# lyte-byte-pcb.net
KiCad netlist of a schematic drawn in EAGLE
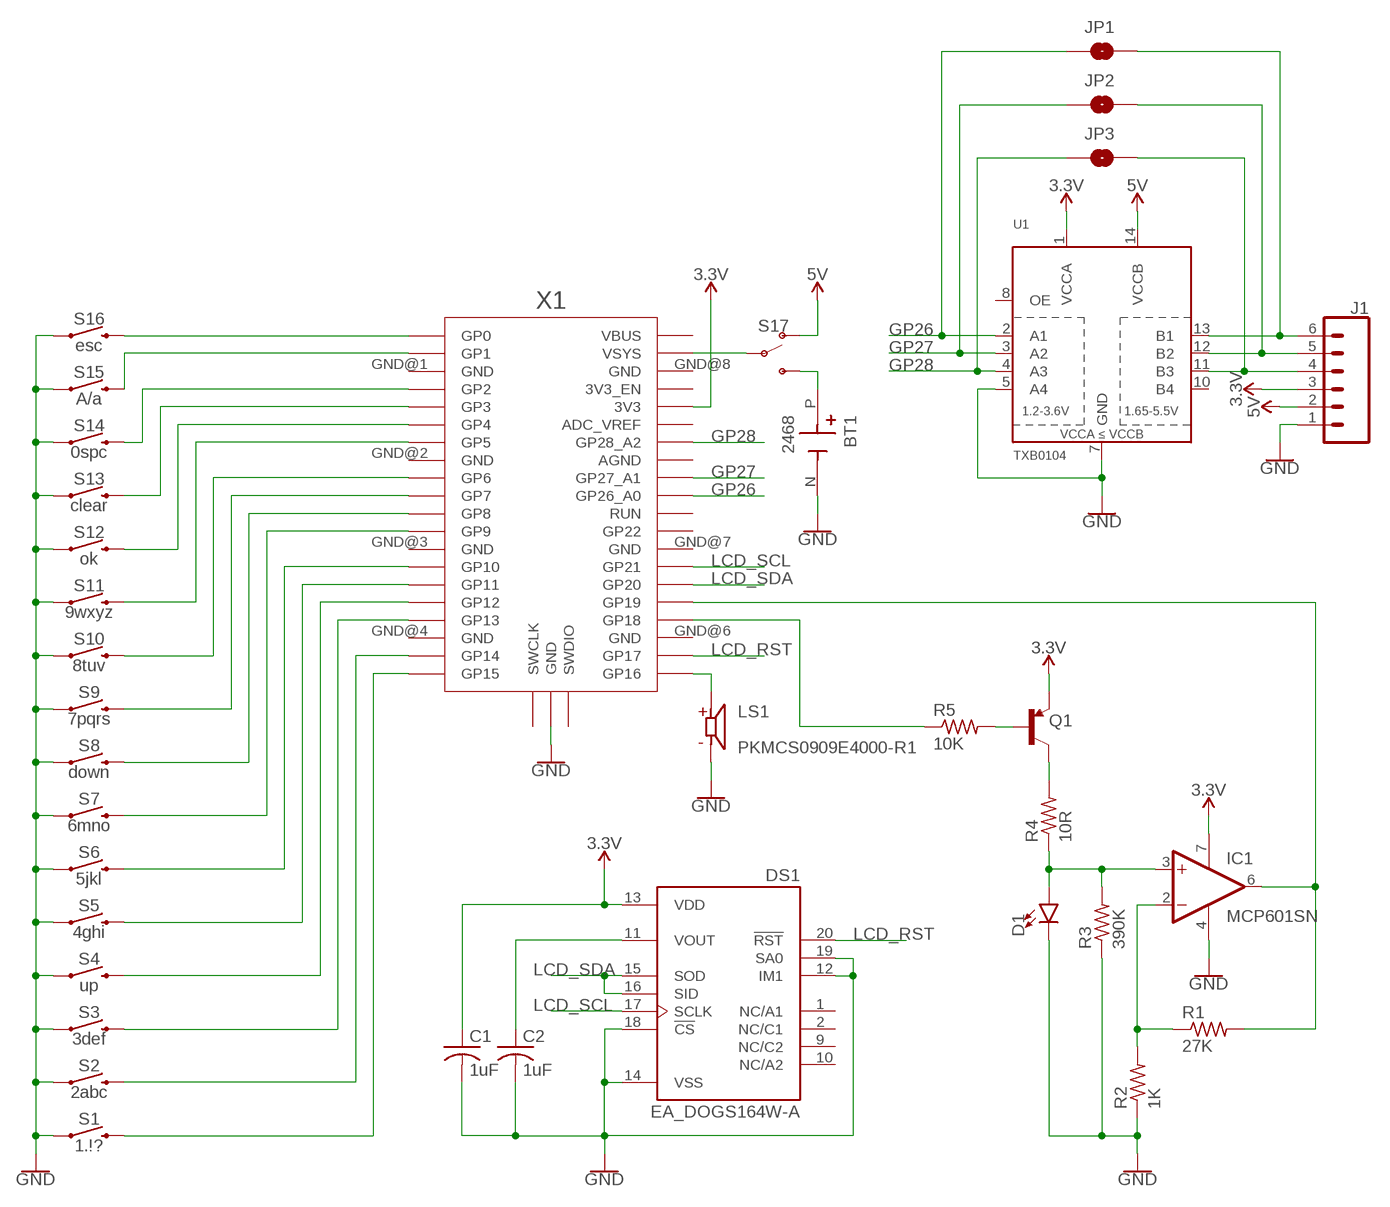
[diagram p0: schematic, sheet 1]

(export (version "E")
  (design (tool "Eeschema 10.0.6"))
  (components
    (comp (ref "BT1")
      (value "2468")
      (footprint "eagle-import:BAT_2468")
      (fields (field (name "MANUFACTURER") "Keystone"))
      (libsource (lib "eagle-import") (part "2468"))
    )
    (comp (ref "C1")
      (value "1uF")
      (footprint "eagle-import:C1206")
      (libsource (lib "eagle-import") (part "C-USC1206"))
    )
    (comp (ref "C2")
      (value "1uF")
      (footprint "eagle-import:C1206")
      (libsource (lib "eagle-import") (part "C-USC1206"))
    )
    (comp (ref "D1")
      (value "LED5MM")
      (footprint "eagle-import:LED_5MM")
      (libsource (lib "eagle-import") (part "LED5MM"))
    )
    (comp (ref "DS1")
      (value "EA_DOGS164W-A")
      (footprint "eagle-import:LCD_EA_DOGS164W-A")
      (fields (field (name "MANUFACTURER") "Display Visions"))
      (libsource (lib "eagle-import") (part "EA_DOGS164W-A"))
    )
    (comp (ref "IC1")
      (value "MCP601SN")
      (footprint "eagle-import:SO08")
      (libsource (lib "eagle-import") (part "MCP601SN"))
    )
    (comp (ref "J1")
      (value "CONN_06SILK_FEMALE_PTH")
      (footprint "eagle-import:1X06")
      (libsource (lib "eagle-import") (part "CONN_06SILK_FEMALE_PTH"))
    )
    (comp (ref "JP1")
      (value "JUMPER-SMT_2_NO_NO-SILK")
      (footprint "eagle-import:SMT-JUMPER_2_NO_NO-SILK")
      (libsource (lib "eagle-import") (part "JUMPER-SMT_2_NO_NO-SILK"))
    )
    (comp (ref "JP2")
      (value "JUMPER-SMT_2_NO_NO-SILK")
      (footprint "eagle-import:SMT-JUMPER_2_NO_NO-SILK")
      (libsource (lib "eagle-import") (part "JUMPER-SMT_2_NO_NO-SILK"))
    )
    (comp (ref "JP3")
      (value "JUMPER-SMT_2_NO_NO-SILK")
      (footprint "eagle-import:SMT-JUMPER_2_NO_NO-SILK")
      (libsource (lib "eagle-import") (part "JUMPER-SMT_2_NO_NO-SILK"))
    )
    (comp (ref "LS1")
      (value "PKMCS0909E4000-R1")
      (footprint "eagle-import:SPKR_PKMCS0909E4000-R1")
      (fields (field (name "MANUFACTURER") "Murata Electronics"))
      (libsource (lib "eagle-import") (part "PKMCS0909E4000-R1"))
    )
    (comp (ref "Q1")
      (value "TRANS_PNP-PMBT3906|MMBT3906L")
      (footprint "eagle-import:SOT23-3")
      (libsource (lib "eagle-import") (part "TRANS_PNP-PMBT3906|MMBT3906L"))
    )
    (comp (ref "R1")
      (value "27K")
      (footprint "eagle-import:R1206")
      (libsource (lib "eagle-import") (part "R-US_R1206"))
    )
    (comp (ref "R2")
      (value "1K")
      (footprint "eagle-import:R1206")
      (libsource (lib "eagle-import") (part "R-US_R1206"))
    )
    (comp (ref "R3")
      (value "390K")
      (footprint "eagle-import:R1206")
      (libsource (lib "eagle-import") (part "R-US_R1206"))
    )
    (comp (ref "R4")
      (value "10R")
      (footprint "eagle-import:R1206")
      (libsource (lib "eagle-import") (part "R-US_R1206"))
    )
    (comp (ref "R5")
      (value "10K")
      (footprint "eagle-import:R1206")
      (libsource (lib "eagle-import") (part "R-US_R1206"))
    )
    (comp (ref "S1")
      (value "1.\\!?")
      (footprint "eagle-import:TACTILE_SWITCH_SMD_5.2MM")
      (libsource (lib "eagle-import") (part "MOMENTARY-SWITCH-SPST-SMD-5.2MM"))
    )
    (comp (ref "S2")
      (value "2abc")
      (footprint "eagle-import:TACTILE_SWITCH_SMD_5.2MM")
      (libsource (lib "eagle-import") (part "MOMENTARY-SWITCH-SPST-SMD-5.2MM"))
    )
    (comp (ref "S3")
      (value "3def")
      (footprint "eagle-import:TACTILE_SWITCH_SMD_5.2MM")
      (libsource (lib "eagle-import") (part "MOMENTARY-SWITCH-SPST-SMD-5.2MM"))
    )
    (comp (ref "S4")
      (value "up")
      (footprint "eagle-import:TACTILE_SWITCH_SMD_5.2MM")
      (libsource (lib "eagle-import") (part "MOMENTARY-SWITCH-SPST-SMD-5.2MM"))
    )
    (comp (ref "S5")
      (value "4ghi")
      (footprint "eagle-import:TACTILE_SWITCH_SMD_5.2MM")
      (libsource (lib "eagle-import") (part "MOMENTARY-SWITCH-SPST-SMD-5.2MM"))
    )
    (comp (ref "S6")
      (value "5jkl")
      (footprint "eagle-import:TACTILE_SWITCH_SMD_5.2MM")
      (libsource (lib "eagle-import") (part "MOMENTARY-SWITCH-SPST-SMD-5.2MM"))
    )
    (comp (ref "S7")
      (value "6mno")
      (footprint "eagle-import:TACTILE_SWITCH_SMD_5.2MM")
      (libsource (lib "eagle-import") (part "MOMENTARY-SWITCH-SPST-SMD-5.2MM"))
    )
    (comp (ref "S8")
      (value "down")
      (footprint "eagle-import:TACTILE_SWITCH_SMD_5.2MM")
      (libsource (lib "eagle-import") (part "MOMENTARY-SWITCH-SPST-SMD-5.2MM"))
    )
    (comp (ref "S9")
      (value "7pqrs")
      (footprint "eagle-import:TACTILE_SWITCH_SMD_5.2MM")
      (libsource (lib "eagle-import") (part "MOMENTARY-SWITCH-SPST-SMD-5.2MM"))
    )
    (comp (ref "S10")
      (value "8tuv")
      (footprint "eagle-import:TACTILE_SWITCH_SMD_5.2MM")
      (libsource (lib "eagle-import") (part "MOMENTARY-SWITCH-SPST-SMD-5.2MM"))
    )
    (comp (ref "S11")
      (value "9wxyz")
      (footprint "eagle-import:TACTILE_SWITCH_SMD_5.2MM")
      (libsource (lib "eagle-import") (part "MOMENTARY-SWITCH-SPST-SMD-5.2MM"))
    )
    (comp (ref "S12")
      (value "ok")
      (footprint "eagle-import:TACTILE_SWITCH_SMD_5.2MM")
      (libsource (lib "eagle-import") (part "MOMENTARY-SWITCH-SPST-SMD-5.2MM"))
    )
    (comp (ref "S13")
      (value "clear")
      (footprint "eagle-import:TACTILE_SWITCH_SMD_5.2MM")
      (libsource (lib "eagle-import") (part "MOMENTARY-SWITCH-SPST-SMD-5.2MM"))
    )
    (comp (ref "S14")
      (value "0spc")
      (footprint "eagle-import:TACTILE_SWITCH_SMD_5.2MM")
      (libsource (lib "eagle-import") (part "MOMENTARY-SWITCH-SPST-SMD-5.2MM"))
    )
    (comp (ref "S15")
      (value "A/a")
      (footprint "eagle-import:TACTILE_SWITCH_SMD_5.2MM")
      (libsource (lib "eagle-import") (part "MOMENTARY-SWITCH-SPST-SMD-5.2MM"))
    )
    (comp (ref "S16")
      (value "esc")
      (footprint "eagle-import:TACTILE_SWITCH_SMD_5.2MM")
      (libsource (lib "eagle-import") (part "MOMENTARY-SWITCH-SPST-SMD-5.2MM"))
    )
    (comp (ref "S17")
      (value "SWITCH-SPDT-SMD-AYZ0202")
      (footprint "eagle-import:SWITCH_DPDT_SMD_AYZ0202")
      (libsource (lib "eagle-import") (part "SWITCH-SPDT-SMD-AYZ0202"))
    )
    (comp (ref "U1")
      (value "TXB0104")
      (footprint "eagle-import:SO14")
      (libsource (lib "eagle-import") (part "TXB0104PWRSOIC14"))
    )
    (comp (ref "X1")
      (value "RPI_PICO_IG-SMD")
      (footprint "eagle-import:RPI_PICO")
      (libsource (lib "eagle-import") (part "RPI_PICO_IG-SMD"))
    )
  )
  (nets
    (net (code "1") (name "/GP26") (class "Default")
      (node (ref "JP1") (pin "1") (pinfunction "1_1") (pintype "passive"))
      (node (ref "U1") (pin "2") (pinfunction "A1_2") (pintype "bidirectional"))
      (node (ref "X1") (pin "GP26_A0") (pinfunction "GP26_A0_GP26_A0") (pintype "bidirectional"))
    )
    (net (code "2") (name "/GP27") (class "Default")
      (node (ref "JP2") (pin "1") (pinfunction "1_1") (pintype "passive"))
      (node (ref "U1") (pin "3") (pinfunction "A2_3") (pintype "bidirectional"))
      (node (ref "X1") (pin "GP27_A1") (pinfunction "GP27_A1_GP27_A1") (pintype "bidirectional"))
    )
    (net (code "3") (name "/GP28") (class "Default")
      (node (ref "JP3") (pin "1") (pinfunction "1_1") (pintype "passive"))
      (node (ref "U1") (pin "4") (pinfunction "A3_4") (pintype "bidirectional"))
      (node (ref "X1") (pin "GP28_A2") (pinfunction "GP28_A2_GP28_A2") (pintype "bidirectional"))
    )
    (net (code "4") (name "/LCD_RST") (class "Default")
      (node (ref "DS1") (pin "20") (pinfunction "~{RST}_20") (pintype "input"))
      (node (ref "X1") (pin "GP17") (pinfunction "GP17_GP17") (pintype "bidirectional"))
    )
    (net (code "5") (name "/LCD_SCL") (class "Default")
      (node (ref "DS1") (pin "17") (pinfunction "SCLK_17") (pintype "input"))
      (node (ref "X1") (pin "GP21") (pinfunction "GP21_GP21") (pintype "bidirectional"))
    )
    (net (code "6") (name "/LCD_SDA") (class "Default")
      (node (ref "DS1") (pin "15") (pinfunction "SOD_15") (pintype "output"))
      (node (ref "DS1") (pin "16") (pinfunction "SID_16") (pintype "input"))
      (node (ref "X1") (pin "GP20") (pinfunction "GP20_GP20") (pintype "bidirectional"))
    )
    (net (code "7") (name "3.3V") (class "Default")
      (node (ref "C1") (pin "1") (pinfunction "1_1") (pintype "passive"))
      (node (ref "DS1") (pin "13") (pinfunction "VDD_13") (pintype "power_in"))
      (node (ref "IC1") (pin "7") (pinfunction "V+_7") (pintype "power_in"))
      (node (ref "J1") (pin "3") (pinfunction "3_3") (pintype "passive"))
      (node (ref "Q1") (pin "2") (pinfunction "E_2") (pintype "passive"))
      (node (ref "U1") (pin "1") (pinfunction "VCCA_1") (pintype "bidirectional"))
      (node (ref "X1") (pin "3V3") (pinfunction "3V3_3V3") (pintype "bidirectional"))
    )
    (net (code "8") (name "5V") (class "Default")
      (node (ref "J1") (pin "2") (pinfunction "2_2") (pintype "passive"))
      (node (ref "S17") (pin "1") (pinfunction "O_1") (pintype "passive"))
      (node (ref "U1") (pin "14") (pinfunction "VCCB_14") (pintype "bidirectional"))
    )
    (net (code "9") (name "GND") (class "Default")
      (node (ref "BT1") (pin "N") (pinfunction "NEG_N") (pintype "passive"))
      (node (ref "C1") (pin "2") (pinfunction "2_2") (pintype "passive"))
      (node (ref "C2") (pin "2") (pinfunction "2_2") (pintype "passive"))
      (node (ref "D1") (pin "K") (pinfunction "C_K") (pintype "passive"))
      (node (ref "DS1") (pin "12") (pinfunction "IM1_12") (pintype "input"))
      (node (ref "DS1") (pin "14") (pinfunction "VSS_14") (pintype "power_in"))
      (node (ref "DS1") (pin "18") (pinfunction "~{CS}_18") (pintype "input"))
      (node (ref "DS1") (pin "19") (pinfunction "SA0_19") (pintype "input"))
      (node (ref "IC1") (pin "4") (pinfunction "V-_4") (pintype "power_in"))
      (node (ref "J1") (pin "1") (pinfunction "1_1") (pintype "passive"))
      (node (ref "LS1") (pin "2") (pinfunction "N_2") (pintype "passive"))
      (node (ref "R2") (pin "1") (pinfunction "1_1") (pintype "passive"))
      (node (ref "R3") (pin "1") (pinfunction "1_1") (pintype "passive"))
      (node (ref "S1") (pin "1") (pinfunction "1_1") (pintype "passive"))
      (node (ref "S10") (pin "1") (pinfunction "1_1") (pintype "passive"))
      (node (ref "S11") (pin "1") (pinfunction "1_1") (pintype "passive"))
      (node (ref "S12") (pin "1") (pinfunction "1_1") (pintype "passive"))
      (node (ref "S13") (pin "1") (pinfunction "1_1") (pintype "passive"))
      (node (ref "S14") (pin "1") (pinfunction "1_1") (pintype "passive"))
      (node (ref "S15") (pin "1") (pinfunction "1_1") (pintype "passive"))
      (node (ref "S16") (pin "1") (pinfunction "1_1") (pintype "passive"))
      (node (ref "S2") (pin "1") (pinfunction "1_1") (pintype "passive"))
      (node (ref "S3") (pin "1") (pinfunction "1_1") (pintype "passive"))
      (node (ref "S4") (pin "1") (pinfunction "1_1") (pintype "passive"))
      (node (ref "S5") (pin "1") (pinfunction "1_1") (pintype "passive"))
      (node (ref "S6") (pin "1") (pinfunction "1_1") (pintype "passive"))
      (node (ref "S7") (pin "1") (pinfunction "1_1") (pintype "passive"))
      (node (ref "S8") (pin "1") (pinfunction "1_1") (pintype "passive"))
      (node (ref "S9") (pin "1") (pinfunction "1_1") (pintype "passive"))
      (node (ref "U1") (pin "5") (pinfunction "A4_5") (pintype "bidirectional"))
      (node (ref "U1") (pin "7") (pinfunction "GND_7") (pintype "bidirectional"))
      (node (ref "X1") (pin "GND@5") (pinfunction "GND_GND@5") (pintype "bidirectional"))
    )
    (net (code "10") (name "Net-(BT1-POS)") (class "Default")
      (node (ref "BT1") (pin "P") (pinfunction "POS_P") (pintype "passive"))
      (node (ref "S17") (pin "3") (pinfunction "S_3") (pintype "passive"))
    )
    (net (code "11") (name "Net-(DS1-VOUT)") (class "Default")
      (node (ref "C2") (pin "1") (pinfunction "1_1") (pintype "passive"))
      (node (ref "DS1") (pin "11") (pinfunction "VOUT_11") (pintype "output"))
    )
    (net (code "12") (name "Net-(IC1-+IN)") (class "Default")
      (node (ref "D1") (pin "A") (pinfunction "A_A") (pintype "passive"))
      (node (ref "IC1") (pin "3") (pinfunction "+IN_3") (pintype "input"))
      (node (ref "R3") (pin "2") (pinfunction "2_2") (pintype "passive"))
      (node (ref "R4") (pin "1") (pinfunction "1_1") (pintype "passive"))
    )
    (net (code "13") (name "Net-(IC1--IN)") (class "Default")
      (node (ref "IC1") (pin "2") (pinfunction "-IN_2") (pintype "input"))
      (node (ref "R1") (pin "1") (pinfunction "1_1") (pintype "passive"))
      (node (ref "R2") (pin "2") (pinfunction "2_2") (pintype "passive"))
    )
    (net (code "14") (name "Net-(IC1-OUT)") (class "Default")
      (node (ref "IC1") (pin "6") (pinfunction "OUT_6") (pintype "output"))
      (node (ref "R1") (pin "2") (pinfunction "2_2") (pintype "passive"))
      (node (ref "X1") (pin "GP19") (pinfunction "GP19_GP19") (pintype "bidirectional"))
    )
    (net (code "15") (name "Net-(LS1-P)") (class "Default")
      (node (ref "LS1") (pin "1") (pinfunction "P_1") (pintype "passive"))
      (node (ref "X1") (pin "GP16") (pinfunction "GP16_GP16") (pintype "bidirectional"))
    )
    (net (code "16") (name "Net-(Q1-B)") (class "Default")
      (node (ref "Q1") (pin "1") (pinfunction "B_1") (pintype "passive"))
      (node (ref "R5") (pin "2") (pinfunction "2_2") (pintype "passive"))
    )
    (net (code "17") (name "Net-(Q1-C)") (class "Default")
      (node (ref "Q1") (pin "3") (pinfunction "C_3") (pintype "passive"))
      (node (ref "R4") (pin "2") (pinfunction "2_2") (pintype "passive"))
    )
    (net (code "18") (name "Net-(R5-Pad1)") (class "Default")
      (node (ref "R5") (pin "1") (pinfunction "1_1") (pintype "passive"))
      (node (ref "X1") (pin "GP18") (pinfunction "GP18_GP18") (pintype "bidirectional"))
    )
    (net (code "19") (name "Net-(S1-2)") (class "Default")
      (node (ref "S1") (pin "3") (pinfunction "2_3") (pintype "passive"))
      (node (ref "X1") (pin "GP15") (pinfunction "GP15_GP15") (pintype "bidirectional"))
    )
    (net (code "20") (name "Net-(S2-2)") (class "Default")
      (node (ref "S2") (pin "3") (pinfunction "2_3") (pintype "passive"))
      (node (ref "X1") (pin "GP14") (pinfunction "GP14_GP14") (pintype "bidirectional"))
    )
    (net (code "21") (name "Net-(S3-2)") (class "Default")
      (node (ref "S3") (pin "3") (pinfunction "2_3") (pintype "passive"))
      (node (ref "X1") (pin "GP13") (pinfunction "GP13_GP13") (pintype "bidirectional"))
    )
    (net (code "22") (name "Net-(S4-2)") (class "Default")
      (node (ref "S4") (pin "3") (pinfunction "2_3") (pintype "passive"))
      (node (ref "X1") (pin "GP12") (pinfunction "GP12_GP12") (pintype "bidirectional"))
    )
    (net (code "23") (name "Net-(S5-2)") (class "Default")
      (node (ref "S5") (pin "3") (pinfunction "2_3") (pintype "passive"))
      (node (ref "X1") (pin "GP11") (pinfunction "GP11_GP11") (pintype "bidirectional"))
    )
    (net (code "24") (name "Net-(S6-2)") (class "Default")
      (node (ref "S6") (pin "3") (pinfunction "2_3") (pintype "passive"))
      (node (ref "X1") (pin "GP10") (pinfunction "GP10_GP10") (pintype "bidirectional"))
    )
    (net (code "25") (name "Net-(S7-2)") (class "Default")
      (node (ref "S7") (pin "3") (pinfunction "2_3") (pintype "passive"))
      (node (ref "X1") (pin "GP9") (pinfunction "GP9_GP9") (pintype "bidirectional"))
    )
    (net (code "26") (name "Net-(S8-2)") (class "Default")
      (node (ref "S8") (pin "3") (pinfunction "2_3") (pintype "passive"))
      (node (ref "X1") (pin "GP8") (pinfunction "GP8_GP8") (pintype "bidirectional"))
    )
    (net (code "27") (name "Net-(S9-2)") (class "Default")
      (node (ref "S9") (pin "3") (pinfunction "2_3") (pintype "passive"))
      (node (ref "X1") (pin "GP7") (pinfunction "GP7_GP7") (pintype "bidirectional"))
    )
    (net (code "28") (name "Net-(S10-2)") (class "Default")
      (node (ref "S10") (pin "3") (pinfunction "2_3") (pintype "passive"))
      (node (ref "X1") (pin "GP6") (pinfunction "GP6_GP6") (pintype "bidirectional"))
    )
    (net (code "29") (name "Net-(S11-2)") (class "Default")
      (node (ref "S11") (pin "3") (pinfunction "2_3") (pintype "passive"))
      (node (ref "X1") (pin "GP5") (pinfunction "GP5_GP5") (pintype "bidirectional"))
    )
    (net (code "30") (name "Net-(S12-2)") (class "Default")
      (node (ref "S12") (pin "3") (pinfunction "2_3") (pintype "passive"))
      (node (ref "X1") (pin "GP4") (pinfunction "GP4_GP4") (pintype "bidirectional"))
    )
    (net (code "31") (name "Net-(S13-2)") (class "Default")
      (node (ref "S13") (pin "3") (pinfunction "2_3") (pintype "passive"))
      (node (ref "X1") (pin "GP3") (pinfunction "GP3_GP3") (pintype "bidirectional"))
    )
    (net (code "32") (name "Net-(S14-2)") (class "Default")
      (node (ref "S14") (pin "3") (pinfunction "2_3") (pintype "passive"))
      (node (ref "X1") (pin "GP2") (pinfunction "GP2_GP2") (pintype "bidirectional"))
    )
    (net (code "33") (name "Net-(S15-2)") (class "Default")
      (node (ref "S15") (pin "3") (pinfunction "2_3") (pintype "passive"))
      (node (ref "X1") (pin "GP1") (pinfunction "GP1_GP1") (pintype "bidirectional"))
    )
    (net (code "34") (name "Net-(S16-2)") (class "Default")
      (node (ref "S16") (pin "3") (pinfunction "2_3") (pintype "passive"))
      (node (ref "X1") (pin "GP0") (pinfunction "GP0_GP0") (pintype "bidirectional"))
    )
    (net (code "35") (name "Net-(S17-P)") (class "Default")
      (node (ref "S17") (pin "2") (pinfunction "P_2") (pintype "passive"))
      (node (ref "X1") (pin "VSYS") (pinfunction "VSYS_VSYS") (pintype "bidirectional"))
    )
    (net (code "36") (name "Net-(U1-B1)") (class "Default")
      (node (ref "J1") (pin "6") (pinfunction "6_6") (pintype "passive"))
      (node (ref "JP1") (pin "2") (pinfunction "2_2") (pintype "passive"))
      (node (ref "U1") (pin "13") (pinfunction "B1_13") (pintype "bidirectional"))
    )
    (net (code "37") (name "Net-(U1-B2)") (class "Default")
      (node (ref "J1") (pin "5") (pinfunction "5_5") (pintype "passive"))
      (node (ref "JP2") (pin "2") (pinfunction "2_2") (pintype "passive"))
      (node (ref "U1") (pin "12") (pinfunction "B2_12") (pintype "bidirectional"))
    )
    (net (code "38") (name "Net-(U1-B3)") (class "Default")
      (node (ref "J1") (pin "4") (pinfunction "4_4") (pintype "passive"))
      (node (ref "JP3") (pin "2") (pinfunction "2_2") (pintype "passive"))
      (node (ref "U1") (pin "11") (pinfunction "B3_11") (pintype "bidirectional"))
    )
    (net (code "39") (name "unconnected-(DS1-NC{slash}A1-Pad1)") (class "Default")
      (node (ref "DS1") (pin "1") (pinfunction "NC/A1_1") (pintype "passive"))
    )
    (net (code "40") (name "unconnected-(DS1-NC{slash}A2-Pad10)") (class "Default")
      (node (ref "DS1") (pin "10") (pinfunction "NC/A2_10") (pintype "passive"))
    )
    (net (code "41") (name "unconnected-(DS1-NC{slash}C1-Pad2)") (class "Default")
      (node (ref "DS1") (pin "2") (pinfunction "NC/C1_2") (pintype "passive"))
    )
    (net (code "42") (name "unconnected-(DS1-NC{slash}C2-Pad9)") (class "Default")
      (node (ref "DS1") (pin "9") (pinfunction "NC/C2_9") (pintype "passive"))
    )
    (net (code "43") (name "unconnected-(U1-B4-Pad10)") (class "Default")
      (node (ref "U1") (pin "10") (pinfunction "B4_10") (pintype "bidirectional"))
    )
    (net (code "44") (name "unconnected-(U1-OE-Pad8)") (class "Default")
      (node (ref "U1") (pin "8") (pinfunction "OE_8") (pintype "bidirectional"))
    )
    (net (code "45") (name "unconnected-(X1-GND-PadGND@1)") (class "Default")
      (node (ref "X1") (pin "GND@1") (pinfunction "GND_GND@1") (pintype "bidirectional"))
    )
    (net (code "46") (name "unconnected-(X1-GND-PadGND@2)") (class "Default")
      (node (ref "X1") (pin "GND@2") (pinfunction "GND_GND@2") (pintype "bidirectional"))
    )
    (net (code "47") (name "unconnected-(X1-GND-PadGND@3)") (class "Default")
      (node (ref "X1") (pin "GND@3") (pinfunction "GND_GND@3") (pintype "bidirectional"))
    )
    (net (code "48") (name "unconnected-(X1-GND-PadGND@4)") (class "Default")
      (node (ref "X1") (pin "GND@4") (pinfunction "GND_GND@4") (pintype "bidirectional"))
    )
    (net (code "49") (name "unconnected-(X1-GND-PadGND@6)") (class "Default")
      (node (ref "X1") (pin "GND@6") (pinfunction "GND_GND@6") (pintype "bidirectional"))
    )
    (net (code "50") (name "unconnected-(X1-GND-PadGND@7)") (class "Default")
      (node (ref "X1") (pin "GND@7") (pinfunction "GND_GND@7") (pintype "bidirectional"))
    )
    (net (code "51") (name "unconnected-(X1-GND-PadGND@8)") (class "Default")
      (node (ref "X1") (pin "GND@8") (pinfunction "GND_GND@8") (pintype "bidirectional"))
    )
    (net (code "52") (name "unconnected-(X1-Pad3V3_EN)") (class "Default")
      (node (ref "X1") (pin "3V3_EN") (pinfunction "3V3_EN_3V3_EN") (pintype "bidirectional"))
    )
    (net (code "53") (name "unconnected-(X1-PadADC_VREF)") (class "Default")
      (node (ref "X1") (pin "ADC_VREF") (pinfunction "ADC_VREF_ADC_VREF") (pintype "bidirectional"))
    )
    (net (code "54") (name "unconnected-(X1-PadAGND)") (class "Default")
      (node (ref "X1") (pin "AGND") (pinfunction "AGND_AGND") (pintype "bidirectional"))
    )
    (net (code "55") (name "unconnected-(X1-PadGP22)") (class "Default")
      (node (ref "X1") (pin "GP22") (pinfunction "GP22_GP22") (pintype "bidirectional"))
    )
    (net (code "56") (name "unconnected-(X1-PadRUN)") (class "Default")
      (node (ref "X1") (pin "RUN") (pinfunction "RUN_RUN") (pintype "bidirectional"))
    )
    (net (code "57") (name "unconnected-(X1-PadSWCLK)") (class "Default")
      (node (ref "X1") (pin "SWCLK") (pinfunction "SWCLK_SWCLK") (pintype "bidirectional"))
    )
    (net (code "58") (name "unconnected-(X1-PadSWDIO)") (class "Default")
      (node (ref "X1") (pin "SWDIO") (pinfunction "SWDIO_SWDIO") (pintype "bidirectional"))
    )
    (net (code "59") (name "unconnected-(X1-PadVBUS)") (class "Default")
      (node (ref "X1") (pin "VBUS") (pinfunction "VBUS_VBUS") (pintype "bidirectional"))
    )
  )
)
